# 4093_quad_lfo.net
KiCad netlist of a schematic drawn in EAGLE
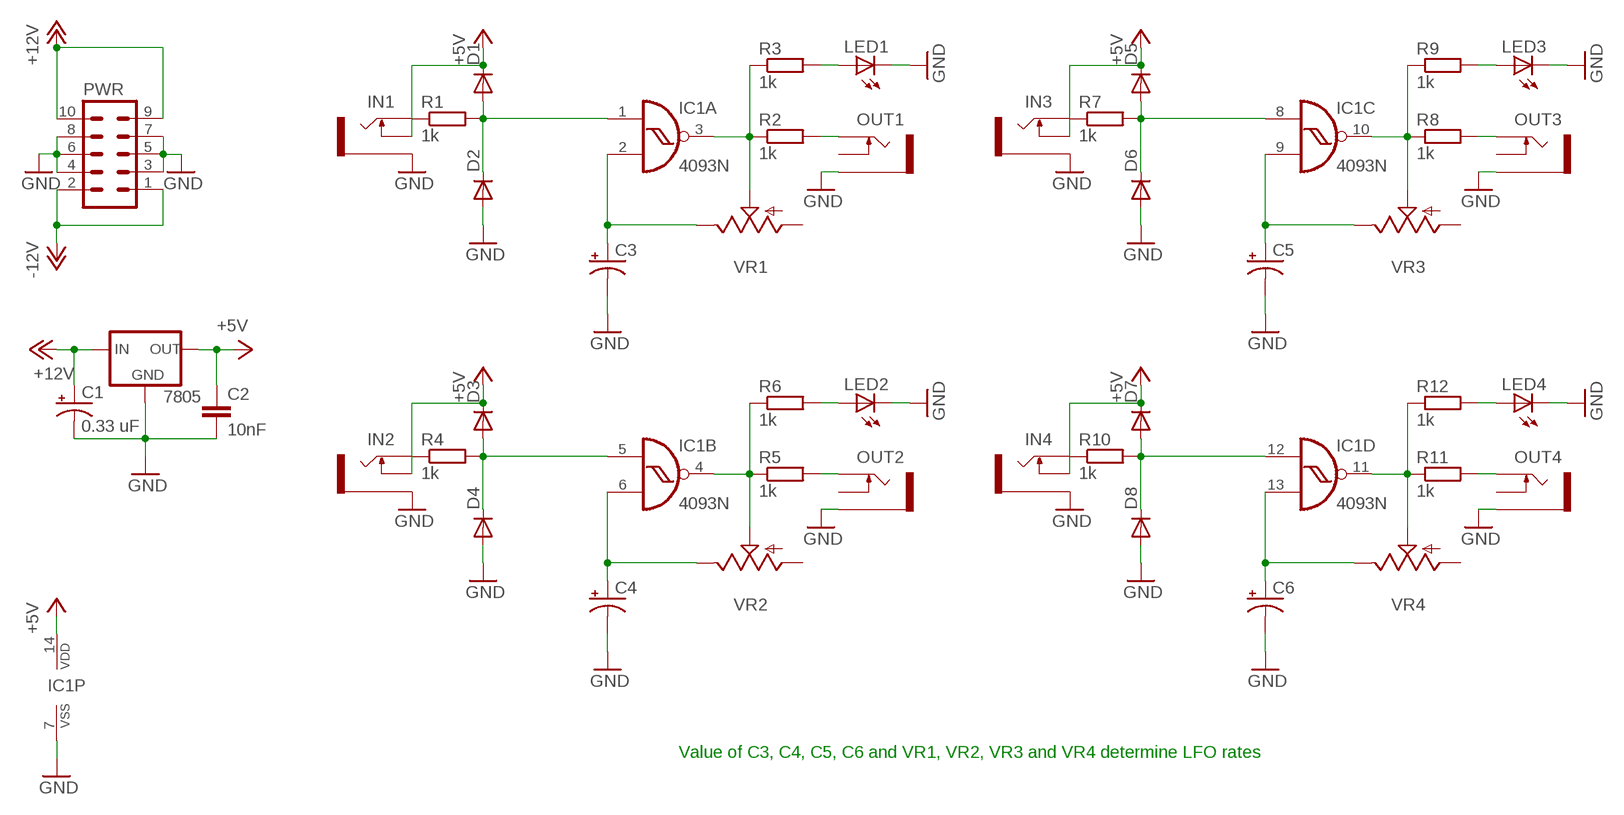
[diagram p0: schematic, sheet 1]

(export (version "E")
  (design (tool "Eeschema 10.0.6"))
  (components
    (comp (ref "7805")
      (value "78XXS")
      (footprint "eagle-import:78XXS")
      (libsource (lib "eagle-import") (part "78XXS"))
    )
    (comp (ref "C1")
      (value "0.33 uF")
      (footprint "eagle-import:E2,5-7")
      (libsource (lib "eagle-import") (part "CPOL-USE2.5-7"))
    )
    (comp (ref "C2")
      (value "10nF")
      (footprint "eagle-import:CAP-PTH-10MM")
      (libsource (lib "eagle-import") (part "10NF-PTH-10MM-10000V-1-%"))
    )
    (comp (ref "C3")
      (value "CPOL-USE2.5-7")
      (footprint "eagle-import:E2,5-7")
      (libsource (lib "eagle-import") (part "CPOL-USE2.5-7"))
    )
    (comp (ref "C4")
      (value "CPOL-USE2.5-7")
      (footprint "eagle-import:E2,5-7")
      (libsource (lib "eagle-import") (part "CPOL-USE2.5-7"))
    )
    (comp (ref "C5")
      (value "CPOL-USE2.5-7")
      (footprint "eagle-import:E2,5-7")
      (libsource (lib "eagle-import") (part "CPOL-USE2.5-7"))
    )
    (comp (ref "C6")
      (value "CPOL-USE2.5-7")
      (footprint "eagle-import:E2,5-7")
      (libsource (lib "eagle-import") (part "CPOL-USE2.5-7"))
    )
    (comp (ref "D1")
      (value "SMALL_DIODEDO35-7")
      (footprint "eagle-import:DO35-7")
      (libsource (lib "eagle-import") (part "SMALL_DIODEDO35-7"))
    )
    (comp (ref "D2")
      (value "SMALL_DIODEDO35-7")
      (footprint "eagle-import:DO35-7")
      (libsource (lib "eagle-import") (part "SMALL_DIODEDO35-7"))
    )
    (comp (ref "D3")
      (value "SMALL_DIODEDO35-7")
      (footprint "eagle-import:DO35-7")
      (libsource (lib "eagle-import") (part "SMALL_DIODEDO35-7"))
    )
    (comp (ref "D4")
      (value "SMALL_DIODEDO35-7")
      (footprint "eagle-import:DO35-7")
      (libsource (lib "eagle-import") (part "SMALL_DIODEDO35-7"))
    )
    (comp (ref "D5")
      (value "SMALL_DIODEDO35-7")
      (footprint "eagle-import:DO35-7")
      (libsource (lib "eagle-import") (part "SMALL_DIODEDO35-7"))
    )
    (comp (ref "D6")
      (value "SMALL_DIODEDO35-7")
      (footprint "eagle-import:DO35-7")
      (libsource (lib "eagle-import") (part "SMALL_DIODEDO35-7"))
    )
    (comp (ref "D7")
      (value "SMALL_DIODEDO35-7")
      (footprint "eagle-import:DO35-7")
      (libsource (lib "eagle-import") (part "SMALL_DIODEDO35-7"))
    )
    (comp (ref "D8")
      (value "SMALL_DIODEDO35-7")
      (footprint "eagle-import:DO35-7")
      (libsource (lib "eagle-import") (part "SMALL_DIODEDO35-7"))
    )
    (comp (ref "IC1")
      (value "4093N")
      (footprint "eagle-import:DIL14")
      (libsource (lib "eagle-import") (part "4093N"))
    )
    (comp (ref "IN1")
      (value "THONKICONNNEW")
      (footprint "eagle-import:WQP-PJ301M-12_JACK")
      (libsource (lib "eagle-import") (part "THONKICONNNEW"))
    )
    (comp (ref "IN2")
      (value "THONKICONNNEW")
      (footprint "eagle-import:WQP-PJ301M-12_JACK")
      (libsource (lib "eagle-import") (part "THONKICONNNEW"))
    )
    (comp (ref "IN3")
      (value "THONKICONNNEW")
      (footprint "eagle-import:WQP-PJ301M-12_JACK")
      (libsource (lib "eagle-import") (part "THONKICONNNEW"))
    )
    (comp (ref "IN4")
      (value "THONKICONNNEW")
      (footprint "eagle-import:WQP-PJ301M-12_JACK")
      (libsource (lib "eagle-import") (part "THONKICONNNEW"))
    )
    (comp (ref "LED1")
      (value "LED3MM")
      (footprint "eagle-import:LED3MM")
      (libsource (lib "eagle-import") (part "LED3MM"))
    )
    (comp (ref "LED2")
      (value "LED3MM")
      (footprint "eagle-import:LED3MM")
      (libsource (lib "eagle-import") (part "LED3MM"))
    )
    (comp (ref "LED3")
      (value "LED3MM")
      (footprint "eagle-import:LED3MM")
      (libsource (lib "eagle-import") (part "LED3MM"))
    )
    (comp (ref "LED4")
      (value "LED3MM")
      (footprint "eagle-import:LED3MM")
      (libsource (lib "eagle-import") (part "LED3MM"))
    )
    (comp (ref "OUT1")
      (value "THONKICONNNEW")
      (footprint "eagle-import:WQP-PJ301M-12_JACK")
      (libsource (lib "eagle-import") (part "THONKICONNNEW"))
    )
    (comp (ref "OUT2")
      (value "THONKICONNNEW")
      (footprint "eagle-import:WQP-PJ301M-12_JACK")
      (libsource (lib "eagle-import") (part "THONKICONNNEW"))
    )
    (comp (ref "OUT3")
      (value "THONKICONNNEW")
      (footprint "eagle-import:WQP-PJ301M-12_JACK")
      (libsource (lib "eagle-import") (part "THONKICONNNEW"))
    )
    (comp (ref "OUT4")
      (value "THONKICONNNEW")
      (footprint "eagle-import:WQP-PJ301M-12_JACK")
      (libsource (lib "eagle-import") (part "THONKICONNNEW"))
    )
    (comp (ref "PWR")
      (value "EURO_POWER_HEADERFAT_PADS")
      (footprint "eagle-import:EURO_PWR_HEADER_FAT")
      (libsource (lib "eagle-import") (part "EURO_POWER_HEADERFAT_PADS"))
    )
    (comp (ref "R1")
      (value "1k")
      (footprint "eagle-import:7MM_RESISTOR")
      (libsource (lib "eagle-import") (part "RESISTOR7MM"))
    )
    (comp (ref "R2")
      (value "1k")
      (footprint "eagle-import:7MM_RESISTOR")
      (libsource (lib "eagle-import") (part "RESISTOR7MM"))
    )
    (comp (ref "R3")
      (value "1k")
      (footprint "eagle-import:7MM_RESISTOR")
      (libsource (lib "eagle-import") (part "RESISTOR7MM"))
    )
    (comp (ref "R4")
      (value "1k")
      (footprint "eagle-import:7MM_RESISTOR")
      (libsource (lib "eagle-import") (part "RESISTOR7MM"))
    )
    (comp (ref "R5")
      (value "1k")
      (footprint "eagle-import:7MM_RESISTOR")
      (libsource (lib "eagle-import") (part "RESISTOR7MM"))
    )
    (comp (ref "R6")
      (value "1k")
      (footprint "eagle-import:7MM_RESISTOR")
      (libsource (lib "eagle-import") (part "RESISTOR7MM"))
    )
    (comp (ref "R7")
      (value "1k")
      (footprint "eagle-import:7MM_RESISTOR")
      (libsource (lib "eagle-import") (part "RESISTOR7MM"))
    )
    (comp (ref "R8")
      (value "1k")
      (footprint "eagle-import:7MM_RESISTOR")
      (libsource (lib "eagle-import") (part "RESISTOR7MM"))
    )
    (comp (ref "R9")
      (value "1k")
      (footprint "eagle-import:7MM_RESISTOR")
      (libsource (lib "eagle-import") (part "RESISTOR7MM"))
    )
    (comp (ref "R10")
      (value "1k")
      (footprint "eagle-import:7MM_RESISTOR")
      (libsource (lib "eagle-import") (part "RESISTOR7MM"))
    )
    (comp (ref "R11")
      (value "1k")
      (footprint "eagle-import:7MM_RESISTOR")
      (libsource (lib "eagle-import") (part "RESISTOR7MM"))
    )
    (comp (ref "R12")
      (value "1k")
      (footprint "eagle-import:7MM_RESISTOR")
      (libsource (lib "eagle-import") (part "RESISTOR7MM"))
    )
    (comp (ref "VR1")
      (value "9MM_SNAP-IN_POT_")
      (footprint "eagle-import:9MM_SNAP-IN_POT")
      (libsource (lib "eagle-import") (part "9MM_SNAP-IN_POT_"))
    )
    (comp (ref "VR2")
      (value "9MM_SNAP-IN_POT_")
      (footprint "eagle-import:9MM_SNAP-IN_POT")
      (libsource (lib "eagle-import") (part "9MM_SNAP-IN_POT_"))
    )
    (comp (ref "VR3")
      (value "9MM_SNAP-IN_POT_")
      (footprint "eagle-import:9MM_SNAP-IN_POT")
      (libsource (lib "eagle-import") (part "9MM_SNAP-IN_POT_"))
    )
    (comp (ref "VR4")
      (value "9MM_SNAP-IN_POT_")
      (footprint "eagle-import:9MM_SNAP-IN_POT")
      (libsource (lib "eagle-import") (part "9MM_SNAP-IN_POT_"))
    )
  )
  (nets
    (net (code "1") (name "+5V") (class "Default")
      (node (ref "7805") (pin "OUT") (pinfunction "OUT_OUT") (pintype "passive"))
      (node (ref "C2") (pin "1") (pinfunction "1_1") (pintype "passive"))
      (node (ref "D1") (pin "C") (pinfunction "C_C") (pintype "passive"))
      (node (ref "D3") (pin "C") (pinfunction "C_C") (pintype "passive"))
      (node (ref "D5") (pin "C") (pinfunction "C_C") (pintype "passive"))
      (node (ref "D7") (pin "C") (pinfunction "C_C") (pintype "passive"))
      (node (ref "IC1") (pin "14") (pinfunction "VDD_14") (pintype "power_in"))
      (node (ref "IN1") (pin "P$2_SWITCH") (pinfunction "SWITCH_P$2_SWITCH") (pintype "passive"))
      (node (ref "IN2") (pin "P$2_SWITCH") (pinfunction "SWITCH_P$2_SWITCH") (pintype "passive"))
      (node (ref "IN3") (pin "P$2_SWITCH") (pinfunction "SWITCH_P$2_SWITCH") (pintype "passive"))
      (node (ref "IN4") (pin "P$2_SWITCH") (pinfunction "SWITCH_P$2_SWITCH") (pintype "passive"))
    )
    (net (code "2") (name "+12V") (class "Default")
      (node (ref "7805") (pin "IN") (pinfunction "IN_IN") (pintype "input"))
      (node (ref "C1") (pin "+") (pinfunction "+_+") (pintype "passive"))
      (node (ref "PWR") (pin "10") (pinfunction "10_10") (pintype "passive"))
      (node (ref "PWR") (pin "9") (pinfunction "9_9") (pintype "passive"))
    )
    (net (code "3") (name "-12V") (class "Default")
      (node (ref "PWR") (pin "1") (pinfunction "1_1") (pintype "passive"))
      (node (ref "PWR") (pin "2") (pinfunction "2_2") (pintype "passive"))
    )
    (net (code "4") (name "GND") (class "Default")
      (node (ref "7805") (pin "GND") (pinfunction "GND_GND") (pintype "input"))
      (node (ref "C1") (pin "-") (pinfunction "-_-") (pintype "passive"))
      (node (ref "C2") (pin "2") (pinfunction "2_2") (pintype "passive"))
      (node (ref "C3") (pin "-") (pinfunction "-_-") (pintype "passive"))
      (node (ref "C4") (pin "-") (pinfunction "-_-") (pintype "passive"))
      (node (ref "C5") (pin "-") (pinfunction "-_-") (pintype "passive"))
      (node (ref "C6") (pin "-") (pinfunction "-_-") (pintype "passive"))
      (node (ref "D2") (pin "A") (pinfunction "A_A") (pintype "passive"))
      (node (ref "D4") (pin "A") (pinfunction "A_A") (pintype "passive"))
      (node (ref "D6") (pin "A") (pinfunction "A_A") (pintype "passive"))
      (node (ref "D8") (pin "A") (pinfunction "A_A") (pintype "passive"))
      (node (ref "IC1") (pin "7") (pinfunction "VSS_7") (pintype "power_in"))
      (node (ref "IN1") (pin "P$3_SLEEVE") (pinfunction "SLEEVE_P$3_SLEEVE") (pintype "passive"))
      (node (ref "IN2") (pin "P$3_SLEEVE") (pinfunction "SLEEVE_P$3_SLEEVE") (pintype "passive"))
      (node (ref "IN3") (pin "P$3_SLEEVE") (pinfunction "SLEEVE_P$3_SLEEVE") (pintype "passive"))
      (node (ref "IN4") (pin "P$3_SLEEVE") (pinfunction "SLEEVE_P$3_SLEEVE") (pintype "passive"))
      (node (ref "LED1") (pin "K") (pinfunction "C_K") (pintype "passive"))
      (node (ref "LED2") (pin "K") (pinfunction "C_K") (pintype "passive"))
      (node (ref "LED3") (pin "K") (pinfunction "C_K") (pintype "passive"))
      (node (ref "LED4") (pin "K") (pinfunction "C_K") (pintype "passive"))
      (node (ref "OUT1") (pin "P$3_SLEEVE") (pinfunction "SLEEVE_P$3_SLEEVE") (pintype "passive"))
      (node (ref "OUT2") (pin "P$3_SLEEVE") (pinfunction "SLEEVE_P$3_SLEEVE") (pintype "passive"))
      (node (ref "OUT3") (pin "P$3_SLEEVE") (pinfunction "SLEEVE_P$3_SLEEVE") (pintype "passive"))
      (node (ref "OUT4") (pin "P$3_SLEEVE") (pinfunction "SLEEVE_P$3_SLEEVE") (pintype "passive"))
      (node (ref "PWR") (pin "3") (pinfunction "3_3") (pintype "passive"))
      (node (ref "PWR") (pin "4") (pinfunction "4_4") (pintype "passive"))
      (node (ref "PWR") (pin "5") (pinfunction "5_5") (pintype "passive"))
      (node (ref "PWR") (pin "6") (pinfunction "6_6") (pintype "passive"))
      (node (ref "PWR") (pin "7") (pinfunction "7_7") (pintype "passive"))
      (node (ref "PWR") (pin "8") (pinfunction "8_8") (pintype "passive"))
    )
    (net (code "5") (name "Net-(IC1A-I0)") (class "Default")
      (node (ref "D1") (pin "A") (pinfunction "A_A") (pintype "passive"))
      (node (ref "D2") (pin "C") (pinfunction "C_C") (pintype "passive"))
      (node (ref "IC1") (pin "1") (pinfunction "I0_1") (pintype "input"))
      (node (ref "R1") (pin "2") (pinfunction "2_2") (pintype "passive"))
    )
    (net (code "6") (name "Net-(IC1A-I1)") (class "Default")
      (node (ref "C3") (pin "+") (pinfunction "+_+") (pintype "passive"))
      (node (ref "IC1") (pin "2") (pinfunction "I1_2") (pintype "input"))
      (node (ref "VR1") (pin "3") (pinfunction "E_3") (pintype "passive"))
    )
    (net (code "7") (name "Net-(IC1A-O)") (class "Default")
      (node (ref "IC1") (pin "3") (pinfunction "O_3") (pintype "output"))
      (node (ref "R2") (pin "1") (pinfunction "1_1") (pintype "passive"))
      (node (ref "R3") (pin "1") (pinfunction "1_1") (pintype "passive"))
      (node (ref "VR1") (pin "2") (pinfunction "S_2") (pintype "passive"))
    )
    (net (code "8") (name "Net-(IC1B-I0)") (class "Default")
      (node (ref "D3") (pin "A") (pinfunction "A_A") (pintype "passive"))
      (node (ref "D4") (pin "C") (pinfunction "C_C") (pintype "passive"))
      (node (ref "IC1") (pin "5") (pinfunction "I0_5") (pintype "input"))
      (node (ref "R4") (pin "2") (pinfunction "2_2") (pintype "passive"))
    )
    (net (code "9") (name "Net-(IC1B-I1)") (class "Default")
      (node (ref "C4") (pin "+") (pinfunction "+_+") (pintype "passive"))
      (node (ref "IC1") (pin "6") (pinfunction "I1_6") (pintype "input"))
      (node (ref "VR2") (pin "3") (pinfunction "E_3") (pintype "passive"))
    )
    (net (code "10") (name "Net-(IC1B-O)") (class "Default")
      (node (ref "IC1") (pin "4") (pinfunction "O_4") (pintype "output"))
      (node (ref "R5") (pin "1") (pinfunction "1_1") (pintype "passive"))
      (node (ref "R6") (pin "1") (pinfunction "1_1") (pintype "passive"))
      (node (ref "VR2") (pin "2") (pinfunction "S_2") (pintype "passive"))
    )
    (net (code "11") (name "Net-(IC1C-I0)") (class "Default")
      (node (ref "D5") (pin "A") (pinfunction "A_A") (pintype "passive"))
      (node (ref "D6") (pin "C") (pinfunction "C_C") (pintype "passive"))
      (node (ref "IC1") (pin "8") (pinfunction "I0_8") (pintype "input"))
      (node (ref "R7") (pin "2") (pinfunction "2_2") (pintype "passive"))
    )
    (net (code "12") (name "Net-(IC1C-I1)") (class "Default")
      (node (ref "C5") (pin "+") (pinfunction "+_+") (pintype "passive"))
      (node (ref "IC1") (pin "9") (pinfunction "I1_9") (pintype "input"))
      (node (ref "VR3") (pin "3") (pinfunction "E_3") (pintype "passive"))
    )
    (net (code "13") (name "Net-(IC1C-O)") (class "Default")
      (node (ref "IC1") (pin "10") (pinfunction "O_10") (pintype "output"))
      (node (ref "R8") (pin "1") (pinfunction "1_1") (pintype "passive"))
      (node (ref "R9") (pin "1") (pinfunction "1_1") (pintype "passive"))
      (node (ref "VR3") (pin "2") (pinfunction "S_2") (pintype "passive"))
    )
    (net (code "14") (name "Net-(IC1D-I0)") (class "Default")
      (node (ref "D7") (pin "A") (pinfunction "A_A") (pintype "passive"))
      (node (ref "D8") (pin "C") (pinfunction "C_C") (pintype "passive"))
      (node (ref "IC1") (pin "12") (pinfunction "I0_12") (pintype "input"))
      (node (ref "R10") (pin "2") (pinfunction "2_2") (pintype "passive"))
    )
    (net (code "15") (name "Net-(IC1D-I1)") (class "Default")
      (node (ref "C6") (pin "+") (pinfunction "+_+") (pintype "passive"))
      (node (ref "IC1") (pin "13") (pinfunction "I1_13") (pintype "input"))
      (node (ref "VR4") (pin "3") (pinfunction "E_3") (pintype "passive"))
    )
    (net (code "16") (name "Net-(IC1D-O)") (class "Default")
      (node (ref "IC1") (pin "11") (pinfunction "O_11") (pintype "output"))
      (node (ref "R11") (pin "1") (pinfunction "1_1") (pintype "passive"))
      (node (ref "R12") (pin "1") (pinfunction "1_1") (pintype "passive"))
      (node (ref "VR4") (pin "2") (pinfunction "S_2") (pintype "passive"))
    )
    (net (code "17") (name "Net-(IN1-TIP)") (class "Default")
      (node (ref "IN1") (pin "P$1_TIP") (pinfunction "TIP_P$1_TIP") (pintype "passive"))
      (node (ref "R1") (pin "1") (pinfunction "1_1") (pintype "passive"))
    )
    (net (code "18") (name "Net-(IN2-TIP)") (class "Default")
      (node (ref "IN2") (pin "P$1_TIP") (pinfunction "TIP_P$1_TIP") (pintype "passive"))
      (node (ref "R4") (pin "1") (pinfunction "1_1") (pintype "passive"))
    )
    (net (code "19") (name "Net-(IN3-TIP)") (class "Default")
      (node (ref "IN3") (pin "P$1_TIP") (pinfunction "TIP_P$1_TIP") (pintype "passive"))
      (node (ref "R7") (pin "1") (pinfunction "1_1") (pintype "passive"))
    )
    (net (code "20") (name "Net-(IN4-TIP)") (class "Default")
      (node (ref "IN4") (pin "P$1_TIP") (pinfunction "TIP_P$1_TIP") (pintype "passive"))
      (node (ref "R10") (pin "1") (pinfunction "1_1") (pintype "passive"))
    )
    (net (code "21") (name "Net-(LED1-PadA)") (class "Default")
      (node (ref "LED1") (pin "A") (pinfunction "A_A") (pintype "passive"))
      (node (ref "R3") (pin "2") (pinfunction "2_2") (pintype "passive"))
    )
    (net (code "22") (name "Net-(LED2-PadA)") (class "Default")
      (node (ref "LED2") (pin "A") (pinfunction "A_A") (pintype "passive"))
      (node (ref "R6") (pin "2") (pinfunction "2_2") (pintype "passive"))
    )
    (net (code "23") (name "Net-(LED3-PadA)") (class "Default")
      (node (ref "LED3") (pin "A") (pinfunction "A_A") (pintype "passive"))
      (node (ref "R9") (pin "2") (pinfunction "2_2") (pintype "passive"))
    )
    (net (code "24") (name "Net-(LED4-PadA)") (class "Default")
      (node (ref "LED4") (pin "A") (pinfunction "A_A") (pintype "passive"))
      (node (ref "R12") (pin "2") (pinfunction "2_2") (pintype "passive"))
    )
    (net (code "25") (name "Net-(OUT1-TIP)") (class "Default")
      (node (ref "OUT1") (pin "P$1_TIP") (pinfunction "TIP_P$1_TIP") (pintype "passive"))
      (node (ref "R2") (pin "2") (pinfunction "2_2") (pintype "passive"))
    )
    (net (code "26") (name "Net-(OUT2-TIP)") (class "Default")
      (node (ref "OUT2") (pin "P$1_TIP") (pinfunction "TIP_P$1_TIP") (pintype "passive"))
      (node (ref "R5") (pin "2") (pinfunction "2_2") (pintype "passive"))
    )
    (net (code "27") (name "Net-(OUT3-TIP)") (class "Default")
      (node (ref "OUT3") (pin "P$1_TIP") (pinfunction "TIP_P$1_TIP") (pintype "passive"))
      (node (ref "R8") (pin "2") (pinfunction "2_2") (pintype "passive"))
    )
    (net (code "28") (name "Net-(OUT4-TIP)") (class "Default")
      (node (ref "OUT4") (pin "P$1_TIP") (pinfunction "TIP_P$1_TIP") (pintype "passive"))
      (node (ref "R11") (pin "2") (pinfunction "2_2") (pintype "passive"))
    )
    (net (code "29") (name "unconnected-(OUT1-SWITCH-PadP$2_SWITCH)") (class "Default")
      (node (ref "OUT1") (pin "P$2_SWITCH") (pinfunction "SWITCH_P$2_SWITCH") (pintype "passive"))
    )
    (net (code "30") (name "unconnected-(OUT2-SWITCH-PadP$2_SWITCH)") (class "Default")
      (node (ref "OUT2") (pin "P$2_SWITCH") (pinfunction "SWITCH_P$2_SWITCH") (pintype "passive"))
    )
    (net (code "31") (name "unconnected-(OUT3-SWITCH-PadP$2_SWITCH)") (class "Default")
      (node (ref "OUT3") (pin "P$2_SWITCH") (pinfunction "SWITCH_P$2_SWITCH") (pintype "passive"))
    )
    (net (code "32") (name "unconnected-(OUT4-SWITCH-PadP$2_SWITCH)") (class "Default")
      (node (ref "OUT4") (pin "P$2_SWITCH") (pinfunction "SWITCH_P$2_SWITCH") (pintype "passive"))
    )
    (net (code "33") (name "unconnected-(VR1-A-Pad1)") (class "Default")
      (node (ref "VR1") (pin "1") (pinfunction "A_1") (pintype "passive"))
    )
    (net (code "34") (name "unconnected-(VR2-A-Pad1)") (class "Default")
      (node (ref "VR2") (pin "1") (pinfunction "A_1") (pintype "passive"))
    )
    (net (code "35") (name "unconnected-(VR3-A-Pad1)") (class "Default")
      (node (ref "VR3") (pin "1") (pinfunction "A_1") (pintype "passive"))
    )
    (net (code "36") (name "unconnected-(VR4-A-Pad1)") (class "Default")
      (node (ref "VR4") (pin "1") (pinfunction "A_1") (pintype "passive"))
    )
  )
)
